# keyboard.net
KiCad netlist of a schematic drawn in EAGLE
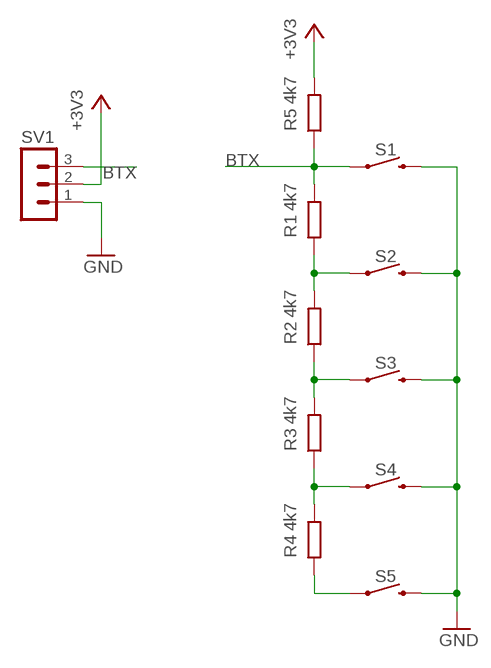
[diagram p0: schematic, sheet 1]

(export (version "E")
  (design (tool "Eeschema 10.0.6"))
  (components
    (comp (ref "R1")
      (value "4k7")
      (footprint "eagle-import:R1206")
      (libsource (lib "eagle-import") (part "R-EU_R1206"))
    )
    (comp (ref "R2")
      (value "4k7")
      (footprint "eagle-import:R1206")
      (libsource (lib "eagle-import") (part "R-EU_R1206"))
    )
    (comp (ref "R3")
      (value "4k7")
      (footprint "eagle-import:R1206")
      (libsource (lib "eagle-import") (part "R-EU_R1206"))
    )
    (comp (ref "R4")
      (value "4k7")
      (footprint "eagle-import:R1206")
      (libsource (lib "eagle-import") (part "R-EU_R1206"))
    )
    (comp (ref "R5")
      (value "4k7")
      (footprint "eagle-import:R1206")
      (libsource (lib "eagle-import") (part "R-EU_R1206"))
    )
    (comp (ref "S1")
      (value "MOMENTARY-SWITCH-SPST-PTH-6.0MM")
      (footprint "eagle-import:TACTILE_SWITCH_PTH_6.0MM")
      (libsource (lib "eagle-import") (part "MOMENTARY-SWITCH-SPST-PTH-6.0MM"))
    )
    (comp (ref "S2")
      (value "MOMENTARY-SWITCH-SPST-PTH-6.0MM")
      (footprint "eagle-import:TACTILE_SWITCH_PTH_6.0MM")
      (libsource (lib "eagle-import") (part "MOMENTARY-SWITCH-SPST-PTH-6.0MM"))
    )
    (comp (ref "S3")
      (value "MOMENTARY-SWITCH-SPST-PTH-6.0MM")
      (footprint "eagle-import:TACTILE_SWITCH_PTH_6.0MM")
      (libsource (lib "eagle-import") (part "MOMENTARY-SWITCH-SPST-PTH-6.0MM"))
    )
    (comp (ref "S4")
      (value "MOMENTARY-SWITCH-SPST-PTH-6.0MM")
      (footprint "eagle-import:TACTILE_SWITCH_PTH_6.0MM")
      (libsource (lib "eagle-import") (part "MOMENTARY-SWITCH-SPST-PTH-6.0MM"))
    )
    (comp (ref "S5")
      (value "MOMENTARY-SWITCH-SPST-PTH-6.0MM")
      (footprint "eagle-import:TACTILE_SWITCH_PTH_6.0MM")
      (libsource (lib "eagle-import") (part "MOMENTARY-SWITCH-SPST-PTH-6.0MM"))
    )
    (comp (ref "SV1")
      (value "MA03-1")
      (footprint "eagle-import:MA03-1")
      (libsource (lib "eagle-import") (part "MA03-1"))
    )
  )
  (nets
    (net (code "1") (name "+3V3") (class "Default")
      (node (ref "R5") (pin "2") (pinfunction "2_2") (pintype "passive"))
      (node (ref "SV1") (pin "2") (pinfunction "2_2") (pintype "passive"))
    )
    (net (code "2") (name "/BTX") (class "Default")
      (node (ref "R1") (pin "2") (pinfunction "2_2") (pintype "passive"))
      (node (ref "R5") (pin "1") (pinfunction "1_1") (pintype "passive"))
      (node (ref "S1") (pin "1") (pinfunction "1_1") (pintype "passive"))
      (node (ref "SV1") (pin "3") (pinfunction "3_3") (pintype "passive"))
    )
    (net (code "3") (name "GND") (class "Default")
      (node (ref "S1") (pin "3") (pinfunction "2_3") (pintype "passive"))
      (node (ref "S2") (pin "3") (pinfunction "2_3") (pintype "passive"))
      (node (ref "S3") (pin "3") (pinfunction "2_3") (pintype "passive"))
      (node (ref "S4") (pin "3") (pinfunction "2_3") (pintype "passive"))
      (node (ref "S5") (pin "3") (pinfunction "2_3") (pintype "passive"))
      (node (ref "SV1") (pin "1") (pinfunction "1_1") (pintype "passive"))
    )
    (net (code "4") (name "Net-(R1-Pad1)") (class "Default")
      (node (ref "R1") (pin "1") (pinfunction "1_1") (pintype "passive"))
      (node (ref "R2") (pin "2") (pinfunction "2_2") (pintype "passive"))
      (node (ref "S2") (pin "1") (pinfunction "1_1") (pintype "passive"))
    )
    (net (code "5") (name "Net-(R2-Pad1)") (class "Default")
      (node (ref "R2") (pin "1") (pinfunction "1_1") (pintype "passive"))
      (node (ref "R3") (pin "2") (pinfunction "2_2") (pintype "passive"))
      (node (ref "S3") (pin "1") (pinfunction "1_1") (pintype "passive"))
    )
    (net (code "6") (name "Net-(R3-Pad1)") (class "Default")
      (node (ref "R3") (pin "1") (pinfunction "1_1") (pintype "passive"))
      (node (ref "R4") (pin "2") (pinfunction "2_2") (pintype "passive"))
      (node (ref "S4") (pin "1") (pinfunction "1_1") (pintype "passive"))
    )
    (net (code "7") (name "Net-(R4-Pad1)") (class "Default")
      (node (ref "R4") (pin "1") (pinfunction "1_1") (pintype "passive"))
      (node (ref "S5") (pin "1") (pinfunction "1_1") (pintype "passive"))
    )
  )
)
